# 05_GAP9_CHIP_GPIO.net
KiCad netlist of a schematic drawn in Altium Designer
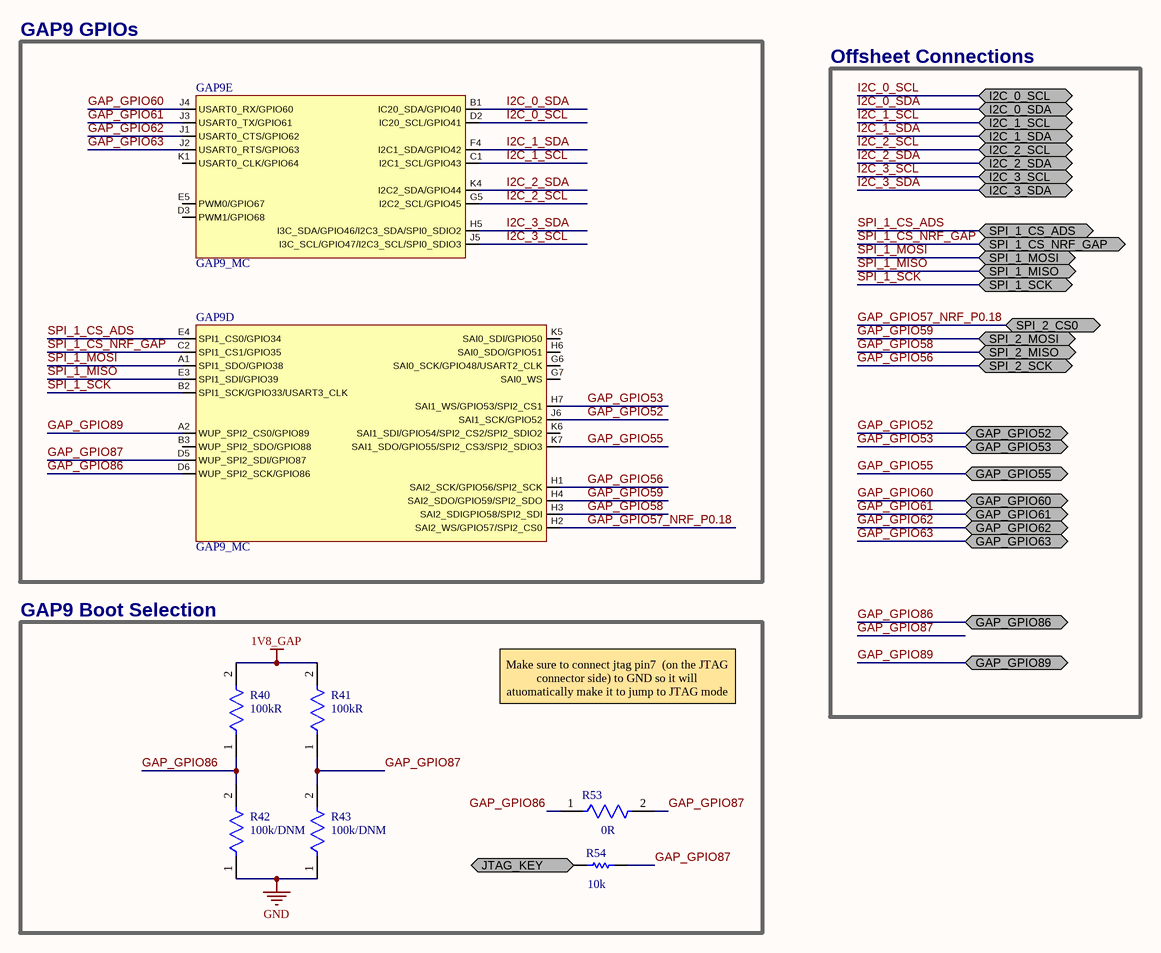
[diagram p0: 05_GAP9_CHIP_GPIO.SchDoc]

(export (version "E")
  (design (tool "Eeschema 10.0.6"))
  (components
    (comp (ref "GAP9") (value "GAP9_MC") (footprint "GAP9") (libsource (lib "EEG_SchLib") (part "GAP9_MC")))
    (comp (ref "R40")
      (value "100kR")
      (footprint "FP-ERJ1GN-IPC_A")
      (description "RES SMD 100K OHM 1% 1/20W 0201")
      (fields (field (name "TOLERANCE") "1%") (field (name "Comment") "ERJ-1GNF1003C"))
      (libsource (lib "Altium Content Vault") (part "1029c3af85768c4190bb7ad29bc67b5"))
    )
    (comp (ref "R41")
      (value "100kR")
      (footprint "FP-ERJ1GN-IPC_A")
      (description "RES SMD 100K OHM 1% 1/20W 0201")
      (fields (field (name "TOLERANCE") "1%") (field (name "Comment") "ERJ-1GNF1003C"))
      (libsource (lib "Altium Content Vault") (part "1029c3af85768c4190bb7ad29bc67b5"))
    )
    (comp (ref "R42")
      (value "100k/DNM")
      (footprint "FP-ERJ1GN-IPC_A")
      (description "RES SMD 100K OHM 1% 1/20W 0201")
      (fields (field (name "TOLERANCE") "1%") (field (name "Comment") "DNM"))
      (libsource (lib "Altium Content Vault") (part "1029c3af85768c4190bb7ad29bc67b5"))
    )
    (comp (ref "R43")
      (value "100k/DNM")
      (footprint "FP-ERJ1GN-IPC_A")
      (description "RES SMD 100K OHM 1% 1/20W 0201")
      (fields (field (name "TOLERANCE") "1%") (field (name "Comment") "DNM"))
      (libsource (lib "Altium Content Vault") (part "1029c3af85768c4190bb7ad29bc67b5"))
    )
    (comp (ref "R53")
      (value "0R")
      (footprint "FP-ERJ1GN-MFG")
      (description "RES SMD 0 OHM JUMPER 1/20W 0201")
      (fields (field (name "TOLERANCE") "1%") (field (name "Comment") "ERJ-1GN0R00C"))
      (libsource (lib "Altium Content Vault") (part "1029c3af85768c4190bb7ad29bc67b5"))
    )
    (comp (ref "R54")
      (value "10k")
      (footprint "RESC0603X28X15LL05T05")
      (fields
        (field (name "MANUFACTURER") "Vishay Dale")
        (field (name "PART NUMBER") "CRCW020110K0FNED")
        (field (name "Comment") "ERJ-U01F1001C")
      )
      (libsource (lib "Altium Content Vault") (part "RES"))
    )
  )
  (nets
    (net (code "1") (name "/GAP_GPIO52") (class "Default")
      (node (ref "GAP9") (pin "J6") (pinfunction "SAI1_SCK/GPIO52_J6") (pintype "passive"))
    )
    (net (code "2") (name "/GAP_GPIO53") (class "Default")
      (node (ref "GAP9") (pin "H7") (pinfunction "SAI1_WS/GPIO53/SPI2_CS1_H7") (pintype "passive"))
    )
    (net (code "3") (name "/GAP_GPIO55") (class "Default")
      (node (ref "GAP9") (pin "K7") (pinfunction "SAI1_SDO/GPIO55/SPI2_CS3/SPI2_SDIO3_K7") (pintype "passive"))
    )
    (net (code "4") (name "/GAP_GPIO56") (class "Default")
      (node (ref "GAP9") (pin "H1") (pinfunction "SAI2_SCK/GPIO56/SPI2_SCK_H1") (pintype "passive"))
    )
    (net (code "5") (name "/GAP_GPIO57_NRF_P0.18") (class "Default")
      (node (ref "GAP9") (pin "H2") (pinfunction "SAI2_WS/GPIO57/SPI2_CS0_H2") (pintype "passive"))
    )
    (net (code "6") (name "/GAP_GPIO58") (class "Default")
      (node (ref "GAP9") (pin "H3") (pinfunction "SAI2_SDIGPIO58/SPI2_SDI_H3") (pintype "passive"))
    )
    (net (code "7") (name "/GAP_GPIO59") (class "Default")
      (node (ref "GAP9") (pin "H4") (pinfunction "SAI2_SDO/GPIO59/SPI2_SDO_H4") (pintype "passive"))
    )
    (net (code "8") (name "/GAP_GPIO60") (class "Default")
      (node (ref "GAP9") (pin "J4") (pinfunction "USART0_RX/GPIO60_J4") (pintype "passive"))
    )
    (net (code "9") (name "/GAP_GPIO61") (class "Default")
      (node (ref "GAP9") (pin "J3") (pinfunction "USART0_TX/GPIO61_J3") (pintype "passive"))
    )
    (net (code "10") (name "/GAP_GPIO62") (class "Default")
      (node (ref "GAP9") (pin "J1") (pinfunction "USART0_CTS/GPIO62_J1") (pintype "passive"))
    )
    (net (code "11") (name "/GAP_GPIO63") (class "Default")
      (node (ref "GAP9") (pin "J2") (pinfunction "USART0_RTS/GPIO63_J2") (pintype "passive"))
    )
    (net (code "12") (name "/GAP_GPIO86") (class "Default")
      (node (ref "GAP9") (pin "D6") (pinfunction "WUP_SPI2_SCK/GPIO86_D6") (pintype "passive"))
      (node (ref "R40") (pin "1") (pinfunction "1_1") (pintype "passive"))
      (node (ref "R42") (pin "2") (pinfunction "2_2") (pintype "passive"))
      (node (ref "R53") (pin "1") (pinfunction "1_1") (pintype "passive"))
    )
    (net (code "13") (name "/GAP_GPIO87") (class "Default")
      (node (ref "GAP9") (pin "D5") (pinfunction "WUP_SPI2_SDI/GPIO87_D5") (pintype "passive"))
      (node (ref "R41") (pin "1") (pinfunction "1_1") (pintype "passive"))
      (node (ref "R43") (pin "2") (pinfunction "2_2") (pintype "passive"))
      (node (ref "R53") (pin "2") (pinfunction "2_2") (pintype "passive"))
      (node (ref "R54") (pin "2") (pinfunction "2_2") (pintype "passive"))
    )
    (net (code "14") (name "/GAP_GPIO89") (class "Default")
      (node (ref "GAP9") (pin "A2") (pinfunction "WUP_SPI2_CS0/GPIO89_A2") (pintype "passive"))
    )
    (net (code "15") (name "/I2C_0_SCL") (class "Default")
      (node (ref "GAP9") (pin "D2") (pinfunction "IC20_SCL/GPIO41_D2") (pintype "passive"))
    )
    (net (code "16") (name "/I2C_0_SDA") (class "Default")
      (node (ref "GAP9") (pin "B1") (pinfunction "IC20_SDA/GPIO40_B1") (pintype "passive"))
    )
    (net (code "17") (name "/I2C_1_SCL") (class "Default")
      (node (ref "GAP9") (pin "C1") (pinfunction "I2C1_SCL/GPIO43_C1") (pintype "passive"))
    )
    (net (code "18") (name "/I2C_1_SDA") (class "Default")
      (node (ref "GAP9") (pin "F4") (pinfunction "I2C1_SDA/GPIO42_F4") (pintype "passive"))
    )
    (net (code "19") (name "/I2C_2_SCL") (class "Default")
      (node (ref "GAP9") (pin "G5") (pinfunction "I2C2_SCL/GPIO45_G5") (pintype "passive"))
    )
    (net (code "20") (name "/I2C_2_SDA") (class "Default")
      (node (ref "GAP9") (pin "K4") (pinfunction "I2C2_SDA/GPIO44_K4") (pintype "passive"))
    )
    (net (code "21") (name "/I2C_3_SCL") (class "Default")
      (node (ref "GAP9") (pin "J5") (pinfunction "I3C_SCL/GPIO47/I2C3_SCL/SPI0_SDIO3_J5") (pintype "passive"))
    )
    (net (code "22") (name "/I2C_3_SDA") (class "Default")
      (node (ref "GAP9") (pin "H5") (pinfunction "I3C_SDA/GPIO46/I2C3_SDA/SPI0_SDIO2_H5") (pintype "passive"))
    )
    (net (code "23") (name "/JTAG_KEY") (class "Default")
      (node (ref "R54") (pin "1") (pinfunction "1_1") (pintype "passive"))
    )
    (net (code "24") (name "/SPI_1_CS_ADS") (class "Default")
      (node (ref "GAP9") (pin "E4") (pinfunction "SPI1_CS0/GPIO34_E4") (pintype "passive"))
    )
    (net (code "25") (name "/SPI_1_CS_NRF_GAP") (class "Default")
      (node (ref "GAP9") (pin "C2") (pinfunction "SPI1_CS1/GPIO35_C2") (pintype "passive"))
    )
    (net (code "26") (name "/SPI_1_MISO") (class "Default")
      (node (ref "GAP9") (pin "E3") (pinfunction "SPI1_SDI/GPIO39_E3") (pintype "passive"))
    )
    (net (code "27") (name "/SPI_1_MOSI") (class "Default")
      (node (ref "GAP9") (pin "A1") (pinfunction "SPI1_SDO/GPIO38_A1") (pintype "passive"))
    )
    (net (code "28") (name "/SPI_1_SCK") (class "Default")
      (node (ref "GAP9") (pin "B2") (pinfunction "SPI1_SCK/GPIO33/USART3_CLK_B2") (pintype "passive"))
    )
    (net (code "29") (name "1V8_GAP") (class "Default")
      (node (ref "R40") (pin "2") (pinfunction "2_2") (pintype "passive"))
      (node (ref "R41") (pin "2") (pinfunction "2_2") (pintype "passive"))
    )
    (net (code "30") (name "GND") (class "Default")
      (node (ref "R42") (pin "1") (pinfunction "1_1") (pintype "passive"))
      (node (ref "R43") (pin "1") (pinfunction "1_1") (pintype "passive"))
    )
    (net (code "31") (name "unconnected-(GAP9D-SAI0_SCK{slash}GPIO48{slash}USART2_CLK-PadG6)") (class "Default")
      (node (ref "GAP9") (pin "G6") (pinfunction "SAI0_SCK/GPIO48/USART2_CLK_G6") (pintype "passive"))
    )
    (net (code "32") (name "unconnected-(GAP9D-SAI0_SDI{slash}GPIO50-PadK5)") (class "Default")
      (node (ref "GAP9") (pin "K5") (pinfunction "SAI0_SDI/GPIO50_K5") (pintype "passive"))
    )
    (net (code "33") (name "unconnected-(GAP9D-SAI0_SDO{slash}GPIO51-PadH6)") (class "Default")
      (node (ref "GAP9") (pin "H6") (pinfunction "SAI0_SDO/GPIO51_H6") (pintype "passive"))
    )
    (net (code "34") (name "unconnected-(GAP9D-SAI0_WS-PadG7)") (class "Default")
      (node (ref "GAP9") (pin "G7") (pinfunction "SAI0_WS_G7") (pintype "passive"))
    )
    (net (code "35") (name "unconnected-(GAP9D-SAI1_SDI{slash}GPIO54{slash}SPI2_CS2{slash}SPI2_SDIO2-PadK6)") (class "Default")
      (node (ref "GAP9") (pin "K6") (pinfunction "SAI1_SDI/GPIO54/SPI2_CS2/SPI2_SDIO2_K6") (pintype "passive"))
    )
    (net (code "36") (name "unconnected-(GAP9D-WUP_SPI2_SDO{slash}GPIO88-PadB3)") (class "Default")
      (node (ref "GAP9") (pin "B3") (pinfunction "WUP_SPI2_SDO/GPIO88_B3") (pintype "passive"))
    )
    (net (code "37") (name "unconnected-(GAP9E-PWM0{slash}GPIO67-PadE5)") (class "Default")
      (node (ref "GAP9") (pin "E5") (pinfunction "PWM0/GPIO67_E5") (pintype "passive"))
    )
    (net (code "38") (name "unconnected-(GAP9E-PWM1{slash}GPIO68-PadD3)") (class "Default")
      (node (ref "GAP9") (pin "D3") (pinfunction "PWM1/GPIO68_D3") (pintype "passive"))
    )
    (net (code "39") (name "unconnected-(GAP9E-USART0_CLK{slash}GPIO64-PadK1)") (class "Default")
      (node (ref "GAP9") (pin "K1") (pinfunction "USART0_CLK/GPIO64_K1") (pintype "passive"))
    )
  )
)
